# Power_Protection_VIN.net
KiCad netlist of a schematic drawn in Altium Designer
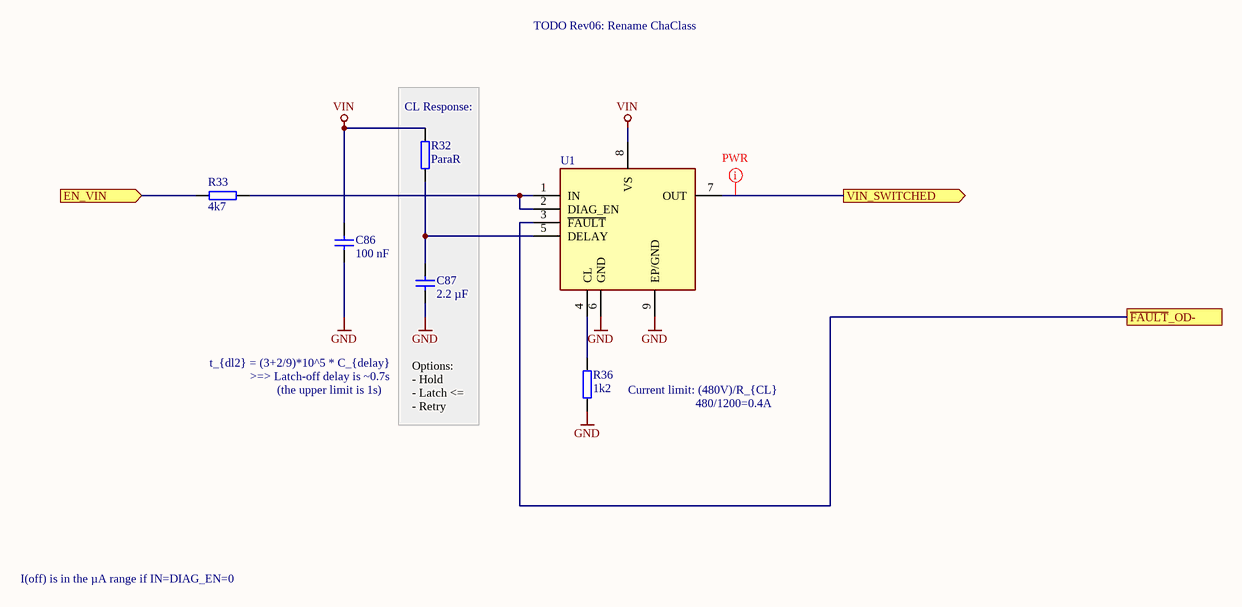
[diagram p0: Power_Protection_VIN.SchDoc]

(export (version "E")
  (design (tool "Eeschema 10.0.6"))
  (components
    (comp (ref "C86")
      (value "100 nF")
      (footprint "C_0603_TE")
      (description "Generic capacitor")
      (fields
        (field (name "MANUFACTURER PART NUMBER") "UZgen_C_0603_100nF_50V_X7R")
        (field (name "MANUFACTURER") "UZgen")
        (field (name "CREATED FROM") "AGeiger")
      )
      (libsource (lib "user") (part "CAP-NP"))
    )
    (comp (ref "C87")
      (value "2.2 µF")
      (footprint "C_0603_TE")
      (description "Generic capacitor")
      (fields
        (field (name "MANUFACTURER PART NUMBER") "UZgen_C_0603_2.2uF_50V_X7R")
        (field (name "MANUFACTURER") "UZgen")
        (field (name "CREATED FROM") "UZgenTool")
      )
      (libsource (lib "user") (part "CAP-NP"))
    )
    (comp (ref "R32")
      (value "ParaR")
      (footprint "R_0603_TE")
      (description "Generic resistor (parametric)")
      (fields
        (field (name "MANUFACTURER PART NUMBER") "UZgen_R_0603_ParaR")
        (field (name "MANUFACTURER") "UZgen")
        (field (name "CREATED FROM") "UZgenTool")
      )
      (libsource (lib "user") (part "RES"))
    )
    (comp (ref "R33")
      (value "4k7")
      (footprint "R_0603_TE")
      (description "Generic resistor")
      (fields
        (field (name "MANUFACTURER PART NUMBER") "UZgen_R_0603_4k7")
        (field (name "MANUFACTURER") "UZgen")
        (field (name "CREATED FROM") "UZgenTool")
      )
      (libsource (lib "user") (part "RES"))
    )
    (comp (ref "R36")
      (value "1k2")
      (footprint "R_0603_TE")
      (description "Generic resistor")
      (fields
        (field (name "MANUFACTURER PART NUMBER") "UZgen_R_0603_1k2")
        (field (name "MANUFACTURER") "UZgen")
        (field (name "CREATED FROM") "UZgenTool")
      )
      (libsource (lib "user") (part "RES"))
    )
    (comp (ref "U1")
      (value "TPS1H000AQDGNRQ1")
      (footprint "SOP65P490X110-9N")
      (fields
        (field (name "MANUFACTURER") "Texas Instruments")
        (field (name "LCSC PART NUMBER") "C2653764")
        (field (name "CREATED FROM") "FRosner")
      )
      (libsource (lib "user") (part "TPS1H000AQDGNRQ1"))
    )
  )
  (nets
    (net (code "1") (name "/EN_VIN") (class "Default")
      (node (ref "R33") (pin "1") (pinfunction "1_1") (pintype "passive"))
    )
    (net (code "2") (name "/VIN_SWITCHED") (class "Default")
      (node (ref "U1") (pin "7") (pinfunction "OUT_7") (pintype "passive"))
    )
    (net (code "3") (name "/~{FAULT}_OD-") (class "Default")
      (node (ref "U1") (pin "3") (pinfunction "~{FAULT}_3") (pintype "passive"))
    )
    (net (code "4") (name "GND") (class "Default")
      (node (ref "C86") (pin "1") (pinfunction "1_1") (pintype "passive"))
      (node (ref "C87") (pin "1") (pinfunction "1_1") (pintype "passive"))
      (node (ref "R36") (pin "1") (pinfunction "1_1") (pintype "passive"))
      (node (ref "U1") (pin "6") (pinfunction "GND_6") (pintype "passive"))
      (node (ref "U1") (pin "9") (pinfunction "EP/GND_9") (pintype "passive"))
    )
    (net (code "5") (name "Net-(U1-CL)") (class "Default")
      (node (ref "R36") (pin "2") (pinfunction "2_2") (pintype "passive"))
      (node (ref "U1") (pin "4") (pinfunction "CL_4") (pintype "passive"))
    )
    (net (code "6") (name "Net-(U1-DELAY)") (class "Default")
      (node (ref "C87") (pin "2") (pinfunction "2_2") (pintype "passive"))
      (node (ref "R32") (pin "1") (pinfunction "1_1") (pintype "passive"))
      (node (ref "U1") (pin "5") (pinfunction "DELAY_5") (pintype "passive"))
    )
    (net (code "7") (name "Net-(U1-DIAG_EN)") (class "Default")
      (node (ref "R33") (pin "2") (pinfunction "2_2") (pintype "passive"))
      (node (ref "U1") (pin "1") (pinfunction "IN_1") (pintype "passive"))
      (node (ref "U1") (pin "2") (pinfunction "DIAG_EN_2") (pintype "passive"))
    )
    (net (code "8") (name "VIN") (class "Default")
      (node (ref "C86") (pin "2") (pinfunction "2_2") (pintype "passive"))
      (node (ref "R32") (pin "2") (pinfunction "2_2") (pintype "passive"))
      (node (ref "U1") (pin "8") (pinfunction "VS_8") (pintype "passive"))
    )
  )
)
